# photoswitch-example.net
KiCad netlist of a schematic drawn in EAGLE
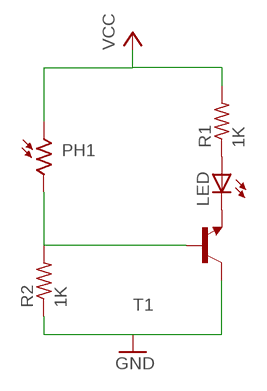
[diagram p0: schematic, sheet 1]

(export (version "E")
  (design (tool "Eeschema 10.0.6"))
  (components
    (comp (ref "LED")
      (value "LED5MM")
      (footprint "eagle-import:LED5MM")
      (libsource (lib "eagle-import") (part "LED5MM"))
    )
    (comp (ref "PH1")
      (value "D1160_12")
      (footprint "eagle-import:D11XX")
      (libsource (lib "eagle-import") (part "D1160_12"))
    )
    (comp (ref "R1")
      (value "1K")
      (footprint "eagle-import:0207_10")
      (libsource (lib "eagle-import") (part "R-US_0207/10"))
    )
    (comp (ref "R2")
      (value "1K")
      (footprint "eagle-import:0207_10")
      (libsource (lib "eagle-import") (part "R-US_0207/10"))
    )
    (comp (ref "T1")
      (value "2N5088")
      (footprint "eagle-import:TO92")
      (libsource (lib "eagle-import") (part "2N5088"))
    )
  )
  (nets
    (net (code "1") (name "GND") (class "Default")
      (node (ref "R2") (pin "1") (pinfunction "1_1") (pintype "passive"))
      (node (ref "T1") (pin "1") (pinfunction "C_1") (pintype "passive"))
    )
    (net (code "2") (name "Net-(LED-C)") (class "Default")
      (node (ref "LED") (pin "K") (pinfunction "C_K") (pintype "passive"))
      (node (ref "T1") (pin "3") (pinfunction "E_3") (pintype "passive"))
    )
    (net (code "3") (name "Net-(LED-PadA)") (class "Default")
      (node (ref "LED") (pin "A") (pinfunction "A_A") (pintype "passive"))
      (node (ref "R1") (pin "1") (pinfunction "1_1") (pintype "passive"))
    )
    (net (code "4") (name "Net-(T1-B)") (class "Default")
      (node (ref "PH1") (pin "2") (pinfunction "2_2") (pintype "passive"))
      (node (ref "R2") (pin "2") (pinfunction "2_2") (pintype "passive"))
      (node (ref "T1") (pin "2") (pinfunction "B_2") (pintype "passive"))
    )
    (net (code "5") (name "VCC") (class "Default")
      (node (ref "PH1") (pin "1") (pinfunction "1_1") (pintype "passive"))
      (node (ref "R1") (pin "2") (pinfunction "2_2") (pintype "passive"))
    )
  )
)
